# 07_ZYNQ_CAMERALINK.net
KiCad netlist of a schematic drawn in Altium Designer
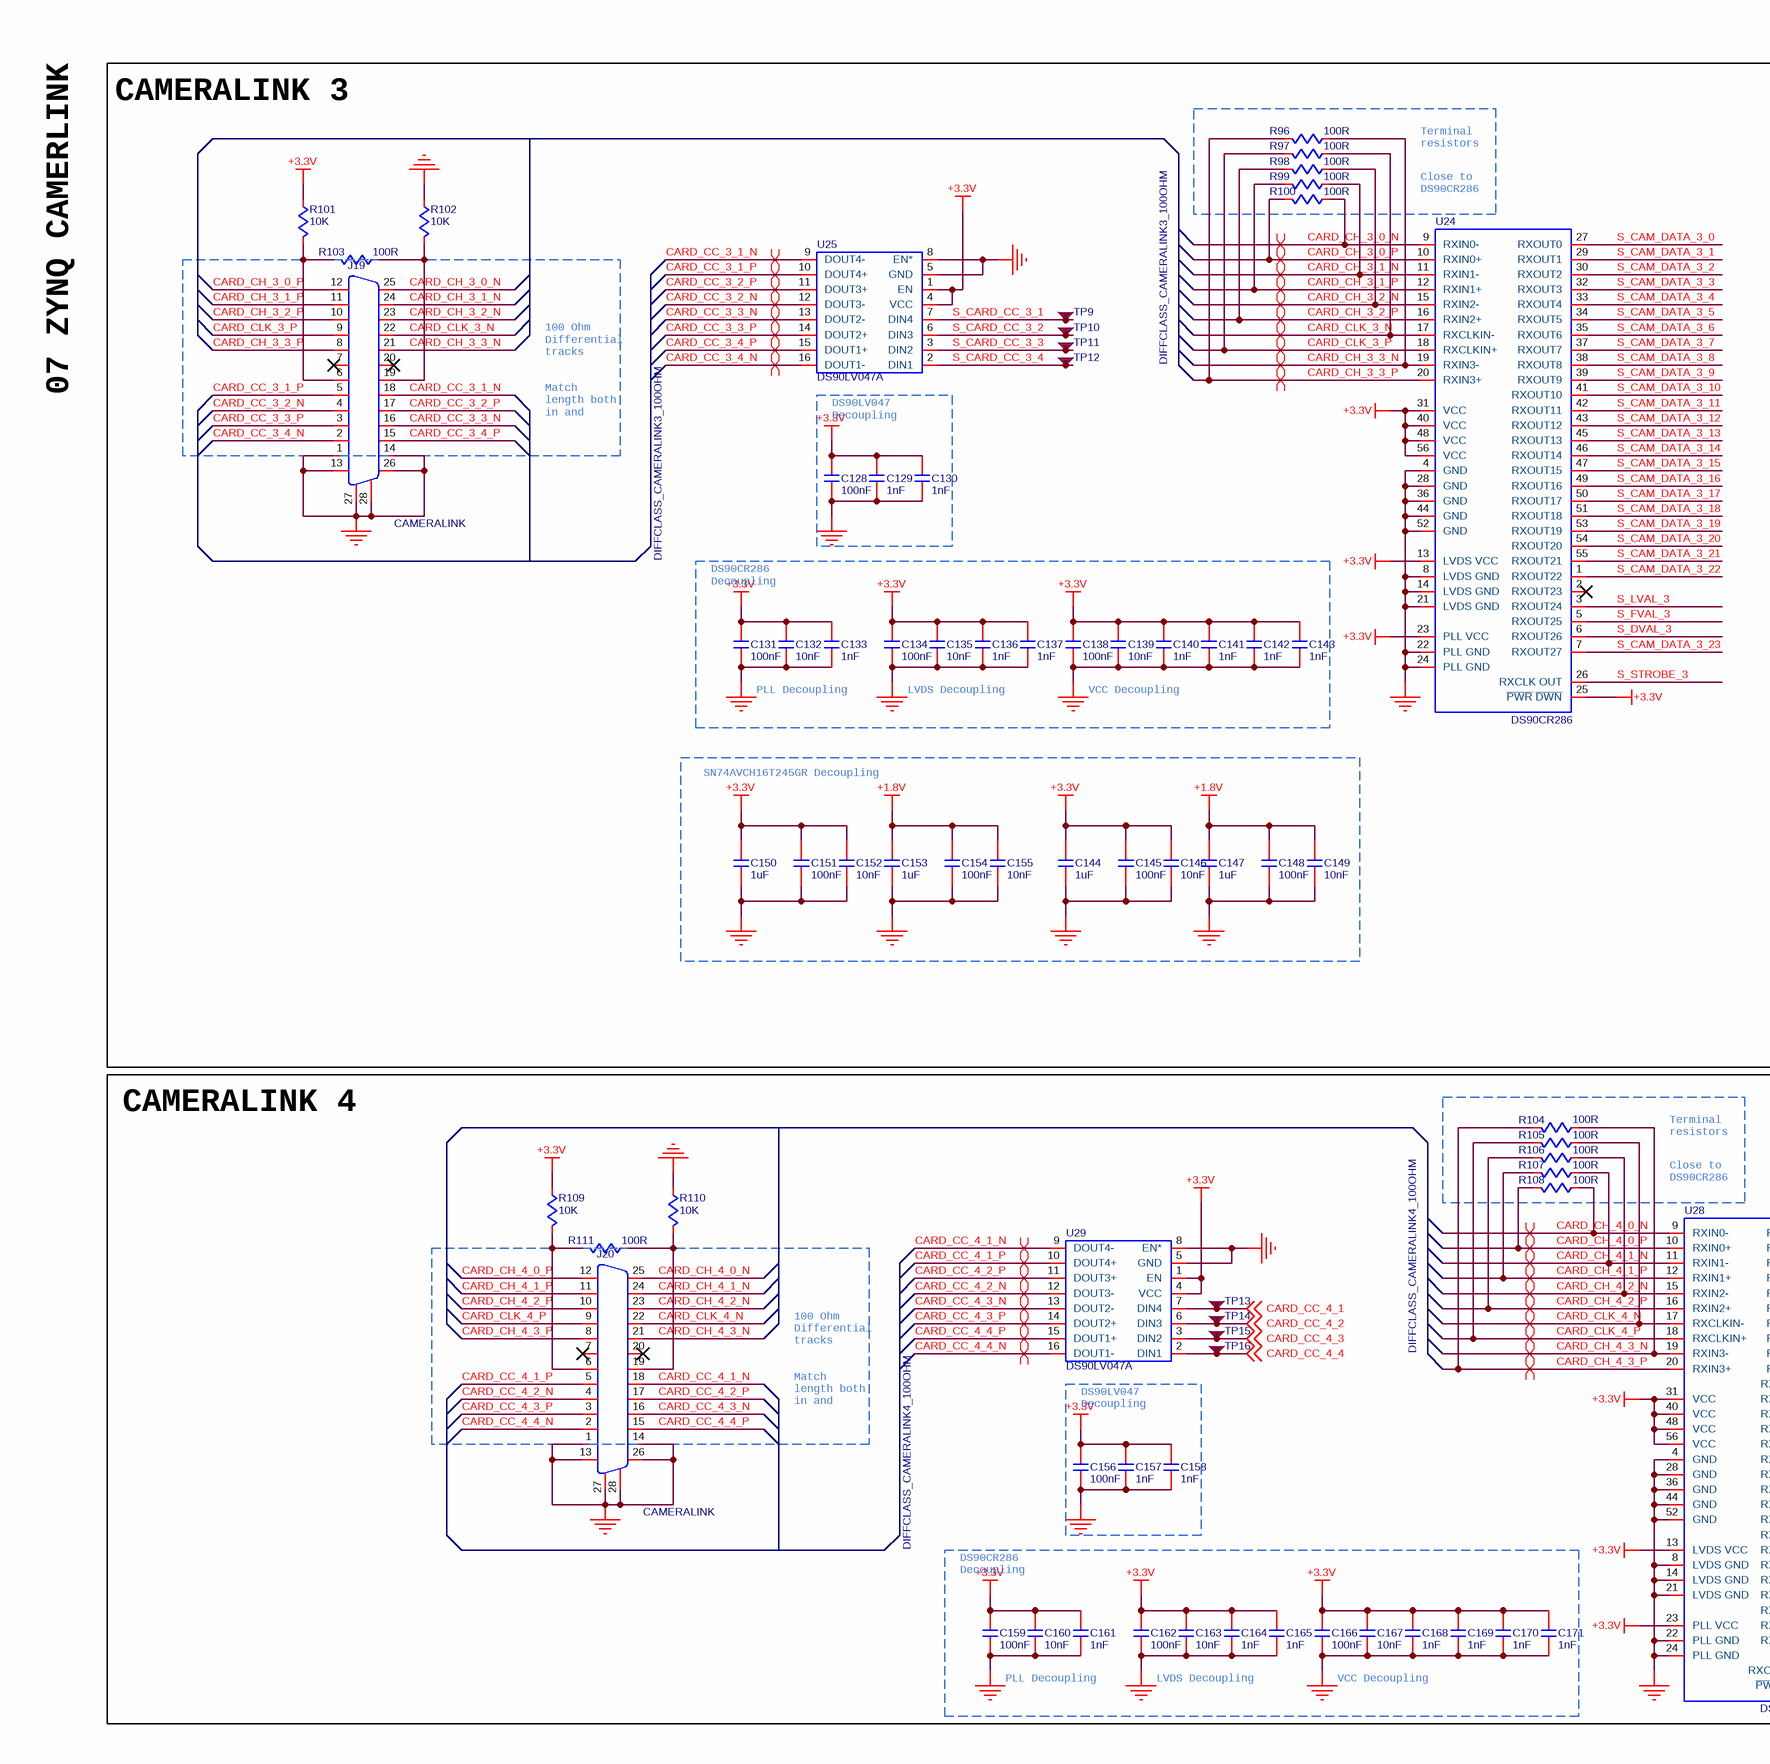
[diagram p0: 07_ZYNQ_CAMERALINK.SchDoc, left]
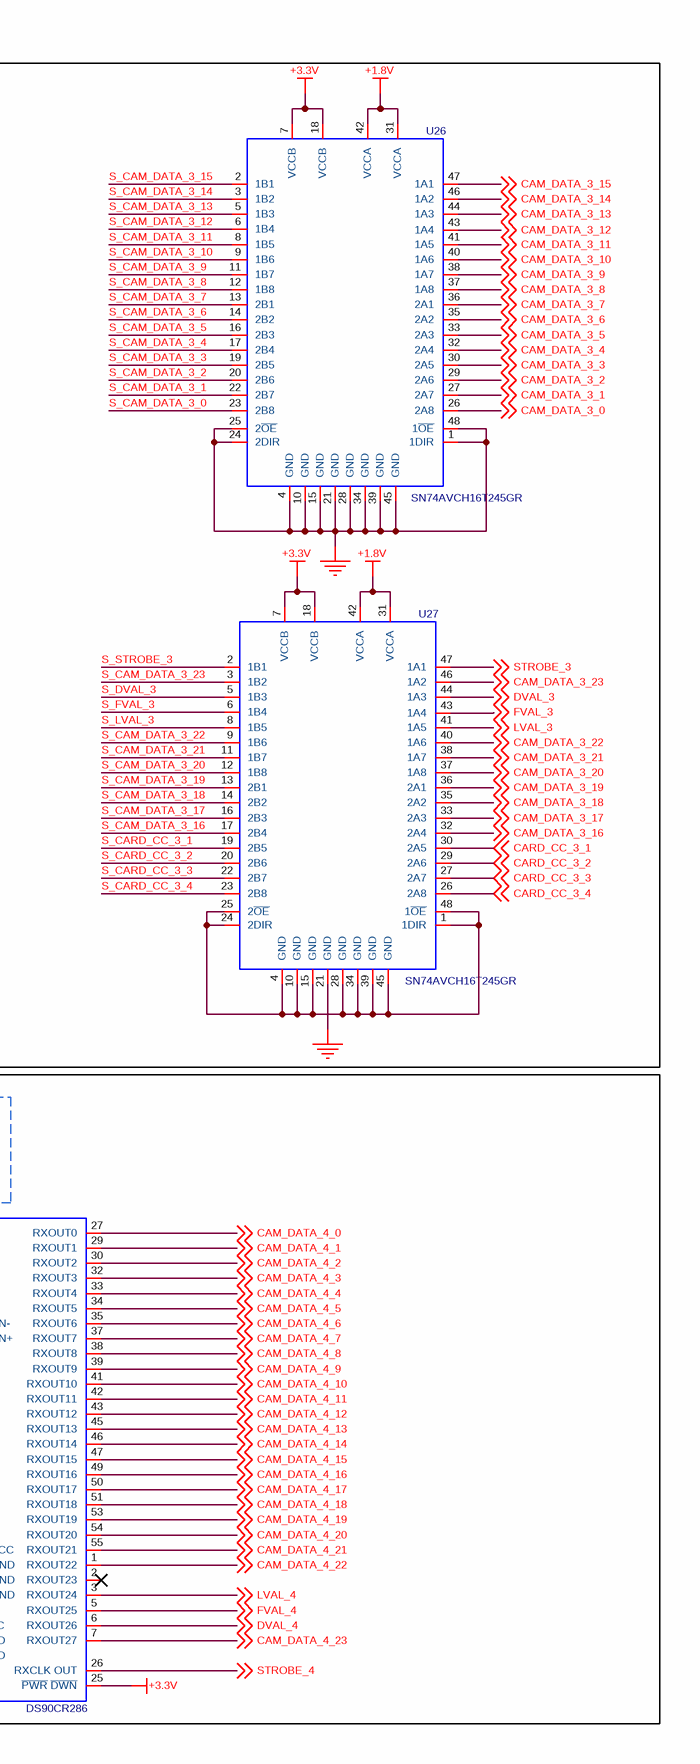
[diagram p1: 07_ZYNQ_CAMERALINK.SchDoc, right]

(export (version "E")
  (design (tool "Eeschema 10.0.6"))
  (components
    (comp (ref "C128")
      (value "100nF")
      (footprint "zynq:C0402")
      (fields (field (name "VOLTAGE") "25V") (field (name "Comment") "C-NOMO"))
      (libsource (lib "zynq") (part "C-NOMO"))
    )
    (comp (ref "C129")
      (value "1nF")
      (footprint "zynq:C0402")
      (fields (field (name "VOLTAGE") "25V") (field (name "Comment") "C-NOMO"))
      (libsource (lib "zynq") (part "C-NOMO"))
    )
    (comp (ref "C130")
      (value "1nF")
      (footprint "zynq:C0402")
      (fields (field (name "VOLTAGE") "25V") (field (name "Comment") "C-NOMO"))
      (libsource (lib "zynq") (part "C-NOMO"))
    )
    (comp (ref "C131")
      (value "100nF")
      (footprint "zynq:C0402")
      (fields (field (name "VOLTAGE") "25V") (field (name "Comment") "C-NOMO"))
      (libsource (lib "zynq") (part "C-NOMO"))
    )
    (comp (ref "C132")
      (value "10nF")
      (footprint "zynq:C0402")
      (fields (field (name "VOLTAGE") "25V") (field (name "Comment") "C-NOMO"))
      (libsource (lib "zynq") (part "C-NOMO"))
    )
    (comp (ref "C133")
      (value "1nF")
      (footprint "zynq:C0402")
      (fields (field (name "VOLTAGE") "25V") (field (name "Comment") "C-NOMO"))
      (libsource (lib "zynq") (part "C-NOMO"))
    )
    (comp (ref "C134")
      (value "100nF")
      (footprint "zynq:C0402")
      (fields (field (name "VOLTAGE") "25V") (field (name "Comment") "C-NOMO"))
      (libsource (lib "zynq") (part "C-NOMO"))
    )
    (comp (ref "C135")
      (value "10nF")
      (footprint "zynq:C0402")
      (fields (field (name "VOLTAGE") "25V") (field (name "Comment") "C-NOMO"))
      (libsource (lib "zynq") (part "C-NOMO"))
    )
    (comp (ref "C136")
      (value "1nF")
      (footprint "zynq:C0402")
      (fields (field (name "VOLTAGE") "25V") (field (name "Comment") "C-NOMO"))
      (libsource (lib "zynq") (part "C-NOMO"))
    )
    (comp (ref "C137")
      (value "1nF")
      (footprint "zynq:C0402")
      (fields (field (name "VOLTAGE") "25V") (field (name "Comment") "C-NOMO"))
      (libsource (lib "zynq") (part "C-NOMO"))
    )
    (comp (ref "C138")
      (value "100nF")
      (footprint "zynq:C0402")
      (fields (field (name "VOLTAGE") "25V") (field (name "Comment") "C-NOMO"))
      (libsource (lib "zynq") (part "C-NOMO"))
    )
    (comp (ref "C139")
      (value "10nF")
      (footprint "zynq:C0402")
      (fields (field (name "VOLTAGE") "25V") (field (name "Comment") "C-NOMO"))
      (libsource (lib "zynq") (part "C-NOMO"))
    )
    (comp (ref "C140")
      (value "1nF")
      (footprint "zynq:C0402")
      (fields (field (name "VOLTAGE") "25V") (field (name "Comment") "C-NOMO"))
      (libsource (lib "zynq") (part "C-NOMO"))
    )
    (comp (ref "C141")
      (value "1nF")
      (footprint "zynq:C0402")
      (fields (field (name "VOLTAGE") "25V") (field (name "Comment") "C-NOMO"))
      (libsource (lib "zynq") (part "C-NOMO"))
    )
    (comp (ref "C142")
      (value "1nF")
      (footprint "zynq:C0402")
      (fields (field (name "VOLTAGE") "25V") (field (name "Comment") "C-NOMO"))
      (libsource (lib "zynq") (part "C-NOMO"))
    )
    (comp (ref "C143")
      (value "1nF")
      (footprint "zynq:C0402")
      (fields (field (name "VOLTAGE") "25V") (field (name "Comment") "C-NOMO"))
      (libsource (lib "zynq") (part "C-NOMO"))
    )
    (comp (ref "C144")
      (value "1uF")
      (footprint "zynq:C0402")
      (fields (field (name "VOLTAGE") "25V") (field (name "Comment") "C-NOMO"))
      (libsource (lib "zynq") (part "C-NOMO"))
    )
    (comp (ref "C145")
      (value "100nF")
      (footprint "zynq:C0402")
      (fields (field (name "VOLTAGE") "25V") (field (name "Comment") "C-NOMO"))
      (libsource (lib "zynq") (part "C-NOMO"))
    )
    (comp (ref "C146")
      (value "10nF")
      (footprint "zynq:C0402")
      (fields (field (name "VOLTAGE") "25V") (field (name "Comment") "C-NOMO"))
      (libsource (lib "zynq") (part "C-NOMO"))
    )
    (comp (ref "C147")
      (value "1uF")
      (footprint "zynq:C0402")
      (fields (field (name "VOLTAGE") "25V") (field (name "Comment") "C-NOMO"))
      (libsource (lib "zynq") (part "C-NOMO"))
    )
    (comp (ref "C148")
      (value "100nF")
      (footprint "zynq:C0402")
      (fields (field (name "VOLTAGE") "25V") (field (name "Comment") "C-NOMO"))
      (libsource (lib "zynq") (part "C-NOMO"))
    )
    (comp (ref "C149")
      (value "10nF")
      (footprint "zynq:C0402")
      (fields (field (name "VOLTAGE") "25V") (field (name "Comment") "C-NOMO"))
      (libsource (lib "zynq") (part "C-NOMO"))
    )
    (comp (ref "C150")
      (value "1uF")
      (footprint "zynq:C0402")
      (fields (field (name "VOLTAGE") "25V") (field (name "Comment") "C-NOMO"))
      (libsource (lib "zynq") (part "C-NOMO"))
    )
    (comp (ref "C151")
      (value "100nF")
      (footprint "zynq:C0402")
      (fields (field (name "VOLTAGE") "25V") (field (name "Comment") "C-NOMO"))
      (libsource (lib "zynq") (part "C-NOMO"))
    )
    (comp (ref "C152")
      (value "10nF")
      (footprint "zynq:C0402")
      (fields (field (name "VOLTAGE") "25V") (field (name "Comment") "C-NOMO"))
      (libsource (lib "zynq") (part "C-NOMO"))
    )
    (comp (ref "C153")
      (value "1uF")
      (footprint "zynq:C0402")
      (fields (field (name "VOLTAGE") "25V") (field (name "Comment") "C-NOMO"))
      (libsource (lib "zynq") (part "C-NOMO"))
    )
    (comp (ref "C154")
      (value "100nF")
      (footprint "zynq:C0402")
      (fields (field (name "VOLTAGE") "25V") (field (name "Comment") "C-NOMO"))
      (libsource (lib "zynq") (part "C-NOMO"))
    )
    (comp (ref "C155")
      (value "10nF")
      (footprint "zynq:C0402")
      (fields (field (name "VOLTAGE") "25V") (field (name "Comment") "C-NOMO"))
      (libsource (lib "zynq") (part "C-NOMO"))
    )
    (comp (ref "C156")
      (value "100nF")
      (footprint "zynq:C0402")
      (fields (field (name "VOLTAGE") "25V") (field (name "Comment") "C-NOMO"))
      (libsource (lib "zynq") (part "C-NOMO"))
    )
    (comp (ref "C157")
      (value "1nF")
      (footprint "zynq:C0402")
      (fields (field (name "VOLTAGE") "25V") (field (name "Comment") "C-NOMO"))
      (libsource (lib "zynq") (part "C-NOMO"))
    )
    (comp (ref "C158")
      (value "1nF")
      (footprint "zynq:C0402")
      (fields (field (name "VOLTAGE") "25V") (field (name "Comment") "C-NOMO"))
      (libsource (lib "zynq") (part "C-NOMO"))
    )
    (comp (ref "C159")
      (value "100nF")
      (footprint "zynq:C0402")
      (fields (field (name "VOLTAGE") "25V") (field (name "Comment") "C-NOMO"))
      (libsource (lib "zynq") (part "C-NOMO"))
    )
    (comp (ref "C160")
      (value "10nF")
      (footprint "zynq:C0402")
      (fields (field (name "VOLTAGE") "25V") (field (name "Comment") "C-NOMO"))
      (libsource (lib "zynq") (part "C-NOMO"))
    )
    (comp (ref "C161")
      (value "1nF")
      (footprint "zynq:C0402")
      (fields (field (name "VOLTAGE") "25V") (field (name "Comment") "C-NOMO"))
      (libsource (lib "zynq") (part "C-NOMO"))
    )
    (comp (ref "C162")
      (value "100nF")
      (footprint "zynq:C0402")
      (fields (field (name "VOLTAGE") "25V") (field (name "Comment") "C-NOMO"))
      (libsource (lib "zynq") (part "C-NOMO"))
    )
    (comp (ref "C163")
      (value "10nF")
      (footprint "zynq:C0402")
      (fields (field (name "VOLTAGE") "25V") (field (name "Comment") "C-NOMO"))
      (libsource (lib "zynq") (part "C-NOMO"))
    )
    (comp (ref "C164")
      (value "1nF")
      (footprint "zynq:C0402")
      (fields (field (name "VOLTAGE") "25V") (field (name "Comment") "C-NOMO"))
      (libsource (lib "zynq") (part "C-NOMO"))
    )
    (comp (ref "C165")
      (value "1nF")
      (footprint "zynq:C0402")
      (fields (field (name "VOLTAGE") "25V") (field (name "Comment") "C-NOMO"))
      (libsource (lib "zynq") (part "C-NOMO"))
    )
    (comp (ref "C166")
      (value "100nF")
      (footprint "zynq:C0402")
      (fields (field (name "VOLTAGE") "25V") (field (name "Comment") "C-NOMO"))
      (libsource (lib "zynq") (part "C-NOMO"))
    )
    (comp (ref "C167")
      (value "10nF")
      (footprint "zynq:C0402")
      (fields (field (name "VOLTAGE") "25V") (field (name "Comment") "C-NOMO"))
      (libsource (lib "zynq") (part "C-NOMO"))
    )
    (comp (ref "C168")
      (value "1nF")
      (footprint "zynq:C0402")
      (fields (field (name "VOLTAGE") "25V") (field (name "Comment") "C-NOMO"))
      (libsource (lib "zynq") (part "C-NOMO"))
    )
    (comp (ref "C169")
      (value "1nF")
      (footprint "zynq:C0402")
      (fields (field (name "VOLTAGE") "25V") (field (name "Comment") "C-NOMO"))
      (libsource (lib "zynq") (part "C-NOMO"))
    )
    (comp (ref "C170")
      (value "1nF")
      (footprint "zynq:C0402")
      (fields (field (name "VOLTAGE") "25V") (field (name "Comment") "C-NOMO"))
      (libsource (lib "zynq") (part "C-NOMO"))
    )
    (comp (ref "C171")
      (value "1nF")
      (footprint "zynq:C0402")
      (fields (field (name "VOLTAGE") "25V") (field (name "Comment") "C-NOMO"))
      (libsource (lib "zynq") (part "C-NOMO"))
    )
    (comp (ref "J19")
      (value "CAMERALINK")
      (footprint "mw:CAMERALINK")
      (libsource (lib "zynq") (part "CAMERALINK"))
    )
    (comp (ref "J20")
      (value "CAMERALINK")
      (footprint "mw:CAMERALINK")
      (libsource (lib "zynq") (part "CAMERALINK"))
    )
    (comp (ref "R96")
      (value "100R")
      (footprint "zynq:R0402")
      (fields (field (name "Comment") "R"))
      (libsource (lib "zynq") (part "R"))
    )
    (comp (ref "R97")
      (value "100R")
      (footprint "zynq:R0402")
      (fields (field (name "Comment") "R"))
      (libsource (lib "zynq") (part "R"))
    )
    (comp (ref "R98")
      (value "100R")
      (footprint "zynq:R0402")
      (fields (field (name "Comment") "R"))
      (libsource (lib "zynq") (part "R"))
    )
    (comp (ref "R99")
      (value "100R")
      (footprint "zynq:R0402")
      (fields (field (name "Comment") "R"))
      (libsource (lib "zynq") (part "R"))
    )
    (comp (ref "R100")
      (value "100R")
      (footprint "zynq:R0402")
      (fields (field (name "Comment") "R"))
      (libsource (lib "zynq") (part "R"))
    )
    (comp (ref "R101")
      (value "10K")
      (footprint "zynq:R0402")
      (fields (field (name "Comment") "R"))
      (libsource (lib "zynq") (part "R"))
    )
    (comp (ref "R102")
      (value "10K")
      (footprint "zynq:R0402")
      (fields (field (name "Comment") "R"))
      (libsource (lib "zynq") (part "R"))
    )
    (comp (ref "R103")
      (value "100R")
      (footprint "zynq:R0402")
      (fields (field (name "Comment") "R"))
      (libsource (lib "zynq") (part "R"))
    )
    (comp (ref "R104")
      (value "100R")
      (footprint "zynq:R0402")
      (fields (field (name "Comment") "R"))
      (libsource (lib "zynq") (part "R"))
    )
    (comp (ref "R105")
      (value "100R")
      (footprint "zynq:R0402")
      (fields (field (name "Comment") "R"))
      (libsource (lib "zynq") (part "R"))
    )
    (comp (ref "R106")
      (value "100R")
      (footprint "zynq:R0402")
      (fields (field (name "Comment") "R"))
      (libsource (lib "zynq") (part "R"))
    )
    (comp (ref "R107")
      (value "100R")
      (footprint "zynq:R0402")
      (fields (field (name "Comment") "R"))
      (libsource (lib "zynq") (part "R"))
    )
    (comp (ref "R108")
      (value "100R")
      (footprint "zynq:R0402")
      (fields (field (name "Comment") "R"))
      (libsource (lib "zynq") (part "R"))
    )
    (comp (ref "R109")
      (value "10K")
      (footprint "zynq:R0402")
      (fields (field (name "Comment") "R"))
      (libsource (lib "zynq") (part "R"))
    )
    (comp (ref "R110")
      (value "10K")
      (footprint "zynq:R0402")
      (fields (field (name "Comment") "R"))
      (libsource (lib "zynq") (part "R"))
    )
    (comp (ref "R111")
      (value "100R")
      (footprint "zynq:R0402")
      (fields (field (name "Comment") "R"))
      (libsource (lib "zynq") (part "R"))
    )
    (comp (ref "TP9") (value "TP") (footprint "zynq:TP") (libsource (lib "zynq") (part "TP")))
    (comp (ref "TP10") (value "TP") (footprint "zynq:TP") (libsource (lib "zynq") (part "TP")))
    (comp (ref "TP11") (value "TP") (footprint "zynq:TP") (libsource (lib "zynq") (part "TP")))
    (comp (ref "TP12") (value "TP") (footprint "zynq:TP") (libsource (lib "zynq") (part "TP")))
    (comp (ref "TP13") (value "TP") (footprint "zynq:TP") (libsource (lib "zynq") (part "TP")))
    (comp (ref "TP14") (value "TP") (footprint "zynq:TP") (libsource (lib "zynq") (part "TP")))
    (comp (ref "TP15") (value "TP") (footprint "zynq:TP") (libsource (lib "zynq") (part "TP")))
    (comp (ref "TP16") (value "TP") (footprint "zynq:TP") (libsource (lib "zynq") (part "TP")))
    (comp (ref "U24")
      (value "DS90CR286")
      (footprint "zynq:DS90CR286")
      (libsource (lib "zynq") (part "DS90CR286"))
    )
    (comp (ref "U25")
      (value "DS90LV047A")
      (footprint "zynq:DS90LV047")
      (libsource (lib "zynq") (part "DS90LV047A"))
    )
    (comp (ref "U26")
      (value "SN74AVCH16T245GR")
      (footprint "SN74AVCH16T245GR")
      (libsource (lib "zynq") (part "SN74AVCH16T245GR"))
    )
    (comp (ref "U27")
      (value "SN74AVCH16T245GR")
      (footprint "SN74AVCH16T245GR")
      (libsource (lib "zynq") (part "SN74AVCH16T245GR"))
    )
    (comp (ref "U28")
      (value "DS90CR286")
      (footprint "zynq:DS90CR286")
      (libsource (lib "zynq") (part "DS90CR286"))
    )
    (comp (ref "U29")
      (value "DS90LV047A")
      (footprint "zynq:DS90LV047")
      (libsource (lib "zynq") (part "DS90LV047A"))
    )
  )
  (nets
    (net (code "1") (name "+1.8V") (class "Default")
      (node (ref "C147") (pin "2") (pinfunction "2_2") (pintype "passive"))
      (node (ref "C148") (pin "2") (pinfunction "2_2") (pintype "passive"))
      (node (ref "C149") (pin "2") (pinfunction "2_2") (pintype "passive"))
      (node (ref "C153") (pin "2") (pinfunction "2_2") (pintype "passive"))
      (node (ref "C154") (pin "2") (pinfunction "2_2") (pintype "passive"))
      (node (ref "C155") (pin "2") (pinfunction "2_2") (pintype "passive"))
      (node (ref "U26") (pin "31") (pinfunction "VCCA_31") (pintype "passive"))
      (node (ref "U26") (pin "42") (pinfunction "VCCA_42") (pintype "passive"))
      (node (ref "U27") (pin "31") (pinfunction "VCCA_31") (pintype "passive"))
      (node (ref "U27") (pin "42") (pinfunction "VCCA_42") (pintype "passive"))
    )
    (net (code "2") (name "+3.3V") (class "Default")
      (node (ref "C128") (pin "2") (pinfunction "2_2") (pintype "passive"))
      (node (ref "C129") (pin "2") (pinfunction "2_2") (pintype "passive"))
      (node (ref "C130") (pin "2") (pinfunction "2_2") (pintype "passive"))
      (node (ref "C131") (pin "2") (pinfunction "2_2") (pintype "passive"))
      (node (ref "C132") (pin "2") (pinfunction "2_2") (pintype "passive"))
      (node (ref "C133") (pin "2") (pinfunction "2_2") (pintype "passive"))
      (node (ref "C134") (pin "2") (pinfunction "2_2") (pintype "passive"))
      (node (ref "C135") (pin "2") (pinfunction "2_2") (pintype "passive"))
      (node (ref "C136") (pin "2") (pinfunction "2_2") (pintype "passive"))
      (node (ref "C137") (pin "2") (pinfunction "2_2") (pintype "passive"))
      (node (ref "C138") (pin "2") (pinfunction "2_2") (pintype "passive"))
      (node (ref "C139") (pin "2") (pinfunction "2_2") (pintype "passive"))
      (node (ref "C140") (pin "2") (pinfunction "2_2") (pintype "passive"))
      (node (ref "C141") (pin "2") (pinfunction "2_2") (pintype "passive"))
      (node (ref "C142") (pin "2") (pinfunction "2_2") (pintype "passive"))
      (node (ref "C143") (pin "2") (pinfunction "2_2") (pintype "passive"))
      (node (ref "C144") (pin "2") (pinfunction "2_2") (pintype "passive"))
      (node (ref "C145") (pin "2") (pinfunction "2_2") (pintype "passive"))
      (node (ref "C146") (pin "2") (pinfunction "2_2") (pintype "passive"))
      (node (ref "C150") (pin "2") (pinfunction "2_2") (pintype "passive"))
      (node (ref "C151") (pin "2") (pinfunction "2_2") (pintype "passive"))
      (node (ref "C152") (pin "2") (pinfunction "2_2") (pintype "passive"))
      (node (ref "C156") (pin "2") (pinfunction "2_2") (pintype "passive"))
      (node (ref "C157") (pin "2") (pinfunction "2_2") (pintype "passive"))
      (node (ref "C158") (pin "2") (pinfunction "2_2") (pintype "passive"))
      (node (ref "C159") (pin "2") (pinfunction "2_2") (pintype "passive"))
      (node (ref "C160") (pin "2") (pinfunction "2_2") (pintype "passive"))
      (node (ref "C161") (pin "2") (pinfunction "2_2") (pintype "passive"))
      (node (ref "C162") (pin "2") (pinfunction "2_2") (pintype "passive"))
      (node (ref "C163") (pin "2") (pinfunction "2_2") (pintype "passive"))
      (node (ref "C164") (pin "2") (pinfunction "2_2") (pintype "passive"))
      (node (ref "C165") (pin "2") (pinfunction "2_2") (pintype "passive"))
      (node (ref "C166") (pin "2") (pinfunction "2_2") (pintype "passive"))
      (node (ref "C167") (pin "2") (pinfunction "2_2") (pintype "passive"))
      (node (ref "C168") (pin "2") (pinfunction "2_2") (pintype "passive"))
      (node (ref "C169") (pin "2") (pinfunction "2_2") (pintype "passive"))
      (node (ref "C170") (pin "2") (pinfunction "2_2") (pintype "passive"))
      (node (ref "C171") (pin "2") (pinfunction "2_2") (pintype "passive"))
      (node (ref "R101") (pin "2") (pinfunction "2_2") (pintype "passive"))
      (node (ref "R109") (pin "2") (pinfunction "2_2") (pintype "passive"))
      (node (ref "U24") (pin "13") (pinfunction "LVDS_VCC_13") (pintype "passive"))
      (node (ref "U24") (pin "23") (pinfunction "PLL_VCC_23") (pintype "passive"))
      (node (ref "U24") (pin "25") (pinfunction "~{PWR}_~{DWN}_25") (pintype "passive"))
      (node (ref "U24") (pin "31") (pinfunction "VCC_31") (pintype "passive"))
      (node (ref "U24") (pin "40") (pinfunction "VCC_40") (pintype "passive"))
      (node (ref "U24") (pin "48") (pinfunction "VCC_48") (pintype "passive"))
      (node (ref "U24") (pin "56") (pinfunction "VCC_56") (pintype "passive"))
      (node (ref "U25") (pin "1") (pinfunction "EN_1") (pintype "passive"))
      (node (ref "U25") (pin "4") (pinfunction "VCC_4") (pintype "passive"))
      (node (ref "U26") (pin "18") (pinfunction "VCCB_18") (pintype "passive"))
      (node (ref "U26") (pin "7") (pinfunction "VCCB_7") (pintype "passive"))
      (node (ref "U27") (pin "18") (pinfunction "VCCB_18") (pintype "passive"))
      (node (ref "U27") (pin "7") (pinfunction "VCCB_7") (pintype "passive"))
      (node (ref "U28") (pin "13") (pinfunction "LVDS_VCC_13") (pintype "passive"))
      (node (ref "U28") (pin "23") (pinfunction "PLL_VCC_23") (pintype "passive"))
      (node (ref "U28") (pin "25") (pinfunction "~{PWR}_~{DWN}_25") (pintype "passive"))
      (node (ref "U28") (pin "31") (pinfunction "VCC_31") (pintype "passive"))
      (node (ref "U28") (pin "40") (pinfunction "VCC_40") (pintype "passive"))
      (node (ref "U28") (pin "48") (pinfunction "VCC_48") (pintype "passive"))
      (node (ref "U28") (pin "56") (pinfunction "VCC_56") (pintype "passive"))
      (node (ref "U29") (pin "1") (pinfunction "EN_1") (pintype "passive"))
      (node (ref "U29") (pin "4") (pinfunction "VCC_4") (pintype "passive"))
    )
    (net (code "3") (name "/CARD_CC_3_1_N") (class "Default")
      (node (ref "J19") (pin "18") (pintype "passive"))
      (node (ref "U25") (pin "9") (pinfunction "DOUT4-_9") (pintype "passive"))
    )
    (net (code "4") (name "/CARD_CC_3_1_P") (class "Default")
      (node (ref "J19") (pin "5") (pintype "passive"))
      (node (ref "U25") (pin "10") (pinfunction "DOUT4+_10") (pintype "passive"))
    )
    (net (code "5") (name "/CARD_CC_3_2_N") (class "Default")
      (node (ref "J19") (pin "4") (pintype "passive"))
      (node (ref "U25") (pin "12") (pinfunction "DOUT3-_12") (pintype "passive"))
    )
    (net (code "6") (name "/CARD_CC_3_2_P") (class "Default")
      (node (ref "J19") (pin "17") (pintype "passive"))
      (node (ref "U25") (pin "11") (pinfunction "DOUT3+_11") (pintype "passive"))
    )
    (net (code "7") (name "/CARD_CC_3_3_N") (class "Default")
      (node (ref "J19") (pin "16") (pintype "passive"))
      (node (ref "U25") (pin "13") (pinfunction "DOUT2-_13") (pintype "passive"))
    )
    (net (code "8") (name "/CARD_CC_3_3_P") (class "Default")
      (node (ref "J19") (pin "3") (pintype "passive"))
      (node (ref "U25") (pin "14") (pinfunction "DOUT2+_14") (pintype "passive"))
    )
    (net (code "9") (name "/CARD_CC_3_4_N") (class "Default")
      (node (ref "J19") (pin "2") (pintype "passive"))
      (node (ref "U25") (pin "16") (pinfunction "DOUT1-_16") (pintype "passive"))
    )
    (net (code "10") (name "/CARD_CC_3_4_P") (class "Default")
      (node (ref "J19") (pin "15") (pintype "passive"))
      (node (ref "U25") (pin "15") (pinfunction "DOUT1+_15") (pintype "passive"))
    )
    (net (code "11") (name "/CARD_CC_4_1_N") (class "Default")
      (node (ref "J20") (pin "18") (pintype "passive"))
      (node (ref "U29") (pin "9") (pinfunction "DOUT4-_9") (pintype "passive"))
    )
    (net (code "12") (name "/CARD_CC_4_1_P") (class "Default")
      (node (ref "J20") (pin "5") (pintype "passive"))
      (node (ref "U29") (pin "10") (pinfunction "DOUT4+_10") (pintype "passive"))
    )
    (net (code "13") (name "/CARD_CC_4_2_N") (class "Default")
      (node (ref "J20") (pin "4") (pintype "passive"))
      (node (ref "U29") (pin "12") (pinfunction "DOUT3-_12") (pintype "passive"))
    )
    (net (code "14") (name "/CARD_CC_4_2_P") (class "Default")
      (node (ref "J20") (pin "17") (pintype "passive"))
      (node (ref "U29") (pin "11") (pinfunction "DOUT3+_11") (pintype "passive"))
    )
    (net (code "15") (name "/CARD_CC_4_3_N") (class "Default")
      (node (ref "J20") (pin "16") (pintype "passive"))
      (node (ref "U29") (pin "13") (pinfunction "DOUT2-_13") (pintype "passive"))
    )
    (net (code "16") (name "/CARD_CC_4_3_P") (class "Default")
      (node (ref "J20") (pin "3") (pintype "passive"))
      (node (ref "U29") (pin "14") (pinfunction "DOUT2+_14") (pintype "passive"))
    )
    (net (code "17") (name "/CARD_CC_4_4_N") (class "Default")
      (node (ref "J20") (pin "2") (pintype "passive"))
      (node (ref "U29") (pin "16") (pinfunction "DOUT1-_16") (pintype "passive"))
    )
    (net (code "18") (name "/CARD_CC_4_4_P") (class "Default")
      (node (ref "J20") (pin "15") (pintype "passive"))
      (node (ref "U29") (pin "15") (pinfunction "DOUT1+_15") (pintype "passive"))
    )
    (net (code "19") (name "/CARD_CH_3_0_N") (class "Default")
      (node (ref "J19") (pin "25") (pintype "passive"))
      (node (ref "R100") (pin "2") (pinfunction "2_2") (pintype "passive"))
      (node (ref "U24") (pin "9") (pinfunction "RXIN0-_9") (pintype "passive"))
    )
    (net (code "20") (name "/CARD_CH_3_0_P") (class "Default")
      (node (ref "J19") (pin "12") (pintype "passive"))
      (node (ref "R100") (pin "1") (pinfunction "1_1") (pintype "passive"))
      (node (ref "U24") (pin "10") (pinfunction "RXIN0+_10") (pintype "passive"))
    )
    (net (code "21") (name "/CARD_CH_3_1_N") (class "Default")
      (node (ref "J19") (pin "24") (pintype "passive"))
      (node (ref "R99") (pin "2") (pinfunction "2_2") (pintype "passive"))
      (node (ref "U24") (pin "11") (pinfunction "RXIN1-_11") (pintype "passive"))
    )
    (net (code "22") (name "/CARD_CH_3_1_P") (class "Default")
      (node (ref "J19") (pin "11") (pintype "passive"))
      (node (ref "R99") (pin "1") (pinfunction "1_1") (pintype "passive"))
      (node (ref "U24") (pin "12") (pinfunction "RXIN1+_12") (pintype "passive"))
    )
    (net (code "23") (name "/CARD_CH_3_2_N") (class "Default")
      (node (ref "J19") (pin "23") (pintype "passive"))
      (node (ref "R98") (pin "2") (pinfunction "2_2") (pintype "passive"))
      (node (ref "U24") (pin "15") (pinfunction "RXIN2-_15") (pintype "passive"))
    )
    (net (code "24") (name "/CARD_CH_3_2_P") (class "Default")
      (node (ref "J19") (pin "10") (pintype "passive"))
      (node (ref "R98") (pin "1") (pinfunction "1_1") (pintype "passive"))
      (node (ref "U24") (pin "16") (pinfunction "RXIN2+_16") (pintype "passive"))
    )
    (net (code "25") (name "/CARD_CH_3_3_N") (class "Default")
      (node (ref "J19") (pin "21") (pintype "passive"))
      (node (ref "R96") (pin "2") (pinfunction "2_2") (pintype "passive"))
      (node (ref "U24") (pin "19") (pinfunction "RXIN3-_19") (pintype "passive"))
    )
    (net (code "26") (name "/CARD_CH_3_3_P") (class "Default")
      (node (ref "J19") (pin "8") (pintype "passive"))
      (node (ref "R96") (pin "1") (pinfunction "1_1") (pintype "passive"))
      (node (ref "U24") (pin "20") (pinfunction "RXIN3+_20") (pintype "passive"))
    )
    (net (code "27") (name "/CARD_CH_4_0_N") (class "Default")
      (node (ref "J20") (pin "25") (pintype "passive"))
      (node (ref "R108") (pin "2") (pinfunction "2_2") (pintype "passive"))
      (node (ref "U28") (pin "9") (pinfunction "RXIN0-_9") (pintype "passive"))
    )
    (net (code "28") (name "/CARD_CH_4_0_P") (class "Default")
      (node (ref "J20") (pin "12") (pintype "passive"))
      (node (ref "R108") (pin "1") (pinfunction "1_1") (pintype "passive"))
      (node (ref "U28") (pin "10") (pinfunction "RXIN0+_10") (pintype "passive"))
    )
    (net (code "29") (name "/CARD_CH_4_1_N") (class "Default")
      (node (ref "J20") (pin "24") (pintype "passive"))
      (node (ref "R107") (pin "2") (pinfunction "2_2") (pintype "passive"))
      (node (ref "U28") (pin "11") (pinfunction "RXIN1-_11") (pintype "passive"))
    )
    (net (code "30") (name "/CARD_CH_4_1_P") (class "Default")
      (node (ref "J20") (pin "11") (pintype "passive"))
      (node (ref "R107") (pin "1") (pinfunction "1_1") (pintype "passive"))
      (node (ref "U28") (pin "12") (pinfunction "RXIN1+_12") (pintype "passive"))
    )
    (net (code "31") (name "/CARD_CH_4_2_N") (class "Default")
      (node (ref "J20") (pin "23") (pintype "passive"))
      (node (ref "R106") (pin "2") (pinfunction "2_2") (pintype "passive"))
      (node (ref "U28") (pin "15") (pinfunction "RXIN2-_15") (pintype "passive"))
    )
    (net (code "32") (name "/CARD_CH_4_2_P") (class "Default")
      (node (ref "J20") (pin "10") (pintype "passive"))
      (node (ref "R106") (pin "1") (pinfunction "1_1") (pintype "passive"))
      (node (ref "U28") (pin "16") (pinfunction "RXIN2+_16") (pintype "passive"))
    )
    (net (code "33") (name "/CARD_CH_4_3_N") (class "Default")
      (node (ref "J20") (pin "21") (pintype "passive"))
      (node (ref "R104") (pin "2") (pinfunction "2_2") (pintype "passive"))
      (node (ref "U28") (pin "19") (pinfunction "RXIN3-_19") (pintype "passive"))
    )
    (net (code "34") (name "/CARD_CH_4_3_P") (class "Default")
      (node (ref "J20") (pin "8") (pintype "passive"))
      (node (ref "R104") (pin "1") (pinfunction "1_1") (pintype "passive"))
      (node (ref "U28") (pin "20") (pinfunction "RXIN3+_20") (pintype "passive"))
    )
    (net (code "35") (name "/CARD_CLK_3_N") (class "Default")
      (node (ref "J19") (pin "22") (pintype "passive"))
      (node (ref "R97") (pin "2") (pinfunction "2_2") (pintype "passive"))
      (node (ref "U24") (pin "17") (pinfunction "RXCLKIN-_17") (pintype "passive"))
    )
    (net (code "36") (name "/CARD_CLK_3_P") (class "Default")
      (node (ref "J19") (pin "9") (pintype "passive"))
      (node (ref "R97") (pin "1") (pinfunction "1_1") (pintype "passive"))
      (node (ref "U24") (pin "18") (pinfunction "RXCLKIN+_18") (pintype "passive"))
    )
    (net (code "37") (name "/CARD_CLK_4_N") (class "Default")
      (node (ref "J20") (pin "22") (pintype "passive"))
      (node (ref "R105") (pin "2") (pinfunction "2_2") (pintype "passive"))
      (node (ref "U28") (pin "17") (pinfunction "RXCLKIN-_17") (pintype "passive"))
    )
    (net (code "38") (name "/CARD_CLK_4_P") (class "Default")
      (node (ref "J20") (pin "9") (pintype "passive"))
      (node (ref "R105") (pin "1") (pinfunction "1_1") (pintype "passive"))
      (node (ref "U28") (pin "18") (pinfunction "RXCLKIN+_18") (pintype "passive"))
    )
    (net (code "39") (name "/S_CAM_DATA_3_0") (class "Default")
      (node (ref "U24") (pin "27") (pinfunction "RXOUT0_27") (pintype "passive"))
      (node (ref "U26") (pin "23") (pinfunction "2B8_23") (pintype "passive"))
    )
    (net (code "40") (name "/S_CAM_DATA_3_1") (class "Default")
      (node (ref "U24") (pin "29") (pinfunction "RXOUT1_29") (pintype "passive"))
      (node (ref "U26") (pin "22") (pinfunction "2B7_22") (pintype "passive"))
    )
    (net (code "41") (name "/S_CAM_DATA_3_2") (class "Default")
      (node (ref "U24") (pin "30") (pinfunction "RXOUT2_30") (pintype "passive"))
      (node (ref "U26") (pin "20") (pinfunction "2B6_20") (pintype "passive"))
    )
    (net (code "42") (name "/S_CAM_DATA_3_3") (class "Default")
      (node (ref "U24") (pin "32") (pinfunction "RXOUT3_32") (pintype "passive"))
      (node (ref "U26") (pin "19") (pinfunction "2B5_19") (pintype "passive"))
    )
    (net (code "43") (name "/S_CAM_DATA_3_4") (class "Default")
      (node (ref "U24") (pin "33") (pinfunction "RXOUT4_33") (pintype "passive"))
      (node (ref "U26") (pin "17") (pinfunction "2B4_17") (pintype "passive"))
    )
    (net (code "44") (name "/S_CAM_DATA_3_5") (class "Default")
      (node (ref "U24") (pin "34") (pinfunction "RXOUT5_34") (pintype "passive"))
      (node (ref "U26") (pin "16") (pinfunction "2B3_16") (pintype "passive"))
    )
    (net (code "45") (name "/S_CAM_DATA_3_6") (class "Default")
      (node (ref "U24") (pin "35") (pinfunction "RXOUT6_35") (pintype "passive"))
      (node (ref "U26") (pin "14") (pinfunction "2B2_14") (pintype "passive"))
    )
    (net (code "46") (name "/S_CAM_DATA_3_7") (class "Default")
      (node (ref "U24") (pin "37") (pinfunction "RXOUT7_37") (pintype "passive"))
      (node (ref "U26") (pin "13") (pinfunction "2B1_13") (pintype "passive"))
    )
    (net (code "47") (name "/S_CAM_DATA_3_8") (class "Default")
      (node (ref "U24") (pin "38") (pinfunction "RXOUT8_38") (pintype "passive"))
      (node (ref "U26") (pin "12") (pinfunction "1B8_12") (pintype "passive"))
    )
    (net (code "48") (name "/S_CAM_DATA_3_9") (class "Default")
      (node (ref "U24") (pin "39") (pinfunction "RXOUT9_39") (pintype "passive"))
      (node (ref "U26") (pin "11") (pinfunction "1B7_11") (pintype "passive"))
    )
    (net (code "49") (name "/S_CAM_DATA_3_10") (class "Default")
      (node (ref "U24") (pin "41") (pinfunction "RXOUT10_41") (pintype "passive"))
      (node (ref "U26") (pin "9") (pinfunction "1B6_9") (pintype "passive"))
    )
    (net (code "50") (name "/S_CAM_DATA_3_11") (class "Default")
      (node (ref "U24") (pin "42") (pinfunction "RXOUT11_42") (pintype "passive"))
      (node (ref "U26") (pin "8") (pinfunction "1B5_8") (pintype "passive"))
    )
    (net (code "51") (name "/S_CAM_DATA_3_12") (class "Default")
      (node (ref "U24") (pin "43") (pinfunction "RXOUT12_43") (pintype "passive"))
      (node (ref "U26") (pin "6") (pinfunction "1B4_6") (pintype "passive"))
    )
    (net (code "52") (name "/S_CAM_DATA_3_13") (class "Default")
      (node (ref "U24") (pin "45") (pinfunction "RXOUT13_45") (pintype "passive"))
      (node (ref "U26") (pin "5") (pinfunction "1B3_5") (pintype "passive"))
    )
    (net (code "53") (name "/S_CAM_DATA_3_14") (class "Default")
      (node (ref "U24") (pin "46") (pinfunction "RXOUT14_46") (pintype "passive"))
      (node (ref "U26") (pin "3") (pinfunction "1B2_3") (pintype "passive"))
    )
    (net (code "54") (name "/S_CAM_DATA_3_15") (class "Default")
      (node (ref "U24") (pin "47") (pinfunction "RXOUT15_47") (pintype "passive"))
      (node (ref "U26") (pin "2") (pinfunction "1B1_2") (pintype "passive"))
    )
    (net (code "55") (name "/S_CAM_DATA_3_16") (class "Default")
      (node (ref "U24") (pin "49") (pinfunction "RXOUT16_49") (pintype "passive"))
      (node (ref "U27") (pin "17") (pinfunction "2B4_17") (pintype "passive"))
    )
    (net (code "56") (name "/S_CAM_DATA_3_17") (class "Default")
      (node (ref "U24") (pin "50") (pinfunction "RXOUT17_50") (pintype "passive"))
      (node (ref "U27") (pin "16") (pinfunction "2B3_16") (pintype "passive"))
    )
    (net (code "57") (name "/S_CAM_DATA_3_18") (class "Default")
      (node (ref "U24") (pin "51") (pinfunction "RXOUT18_51") (pintype "passive"))
      (node (ref "U27") (pin "14") (pinfunction "2B2_14") (pintype "passive"))
    )
    (net (code "58") (name "/S_CAM_DATA_3_19") (class "Default")
      (node (ref "U24") (pin "53") (pinfunction "RXOUT19_53") (pintype "passive"))
      (node (ref "U27") (pin "13") (pinfunction "2B1_13") (pintype "passive"))
    )
    (net (code "59") (name "/S_CAM_DATA_3_20") (class "Default")
      (node (ref "U24") (pin "54") (pinfunction "RXOUT20_54") (pintype "passive"))
      (node (ref "U27") (pin "12") (pinfunction "1B8_12") (pintype "passive"))
    )
    (net (code "60") (name "/S_CAM_DATA_3_21") (class "Default")
      (node (ref "U24") (pin "55") (pinfunction "RXOUT21_55") (pintype "passive"))
      (node (ref "U27") (pin "11") (pinfunction "1B7_11") (pintype "passive"))
    )
    (net (code "61") (name "/S_CAM_DATA_3_22") (class "Default")
      (node (ref "U24") (pin "1") (pinfunction "RXOUT22_1") (pintype "passive"))
      (node (ref "U27") (pin "9") (pinfunction "1B6_9") (pintype "passive"))
    )
    (net (code "62") (name "/S_CAM_DATA_3_23") (class "Default")
      (node (ref "U24") (pin "7") (pinfunction "RXOUT27_7") (pintype "passive"))
      (node (ref "U27") (pin "3") (pinfunction "1B2_3") (pintype "passive"))
    )
    (net (code "63") (name "/S_CARD_CC_3_1") (class "Default")
      (node (ref "TP9") (pin "0") (pintype "passive"))
      (node (ref "U25") (pin "7") (pinfunction "DIN4_7") (pintype "passive"))
      (node (ref "U27") (pin "19") (pinfunction "2B5_19") (pintype "passive"))
    )
    (net (code "64") (name "/S_CARD_CC_3_2") (class "Default")
      (node (ref "TP10") (pin "0") (pintype "passive"))
      (node (ref "U25") (pin "6") (pinfunction "DIN3_6") (pintype "passive"))
      (node (ref "U27") (pin "20") (pinfunction "2B6_20") (pintype "passive"))
    )
    (net (code "65") (name "/S_CARD_CC_3_3") (class "Default")
      (node (ref "TP11") (pin "0") (pintype "passive"))
      (node (ref "U25") (pin "3") (pinfunction "DIN2_3") (pintype "passive"))
      (node (ref "U27") (pin "22") (pinfunction "2B7_22") (pintype "passive"))
    )
    (net (code "66") (name "/S_CARD_CC_3_4") (class "Default")
      (node (ref "TP12") (pin "0") (pintype "passive"))
      (node (ref "U25") (pin "2") (pinfunction "DIN1_2") (pintype "passive"))
      (node (ref "U27") (pin "23") (pinfunction "2B8_23") (pintype "passive"))
    )
    (net (code "67") (name "/S_DVAL_3") (class "Default")
      (node (ref "U24") (pin "6") (pinfunction "RXOUT26_6") (pintype "passive"))
      (node (ref "U27") (pin "5") (pinfunction "1B3_5") (pintype "passive"))
    )
    (net (code "68") (name "/S_FVAL_3") (class "Default")
      (node (ref "U24") (pin "5") (pinfunction "RXOUT25_5") (pintype "passive"))
      (node (ref "U27") (pin "6") (pinfunction "1B4_6") (pintype "passive"))
    )
    (net (code "69") (name "/S_LVAL_3") (class "Default")
      (node (ref "U24") (pin "3") (pinfunction "RXOUT24_3") (pintype "passive"))
      (node (ref "U27") (pin "8") (pinfunction "1B5_8") (pintype "passive"))
    )
    (net (code "70") (name "/S_STROBE_3") (class "Default")
      (node (ref "U24") (pin "26") (pinfunction "RXCLK_OUT_26") (pintype "passive"))
      (node (ref "U27") (pin "2") (pinfunction "1B1_2") (pintype "passive"))
    )
    (net (code "71") (name "CAM_DATA_3_0") (class "Default")
      (node (ref "U26") (pin "26") (pinfunction "2A8_26") (pintype "passive"))
    )
    (net (code "72") (name "CAM_DATA_3_1") (class "Default")
      (node (ref "U26") (pin "27") (pinfunction "2A7_27") (pintype "passive"))
    )
    (net (code "73") (name "CAM_DATA_3_2") (class "Default")
      (node (ref "U26") (pin "29") (pinfunction "2A6_29") (pintype "passive"))
    )
    (net (code "74") (name "CAM_DATA_3_3") (class "Default")
      (node (ref "U26") (pin "30") (pinfunction "2A5_30") (pintype "passive"))
    )
    (net (code "75") (name "CAM_DATA_3_4") (class "Default")
      (node (ref "U26") (pin "32") (pinfunction "2A4_32") (pintype "passive"))
    )
    (net (code "76") (name "CAM_DATA_3_5") (class "Default")
      (node (ref "U26") (pin "33") (pinfunction "2A3_33") (pintype "passive"))
    )
    (net (code "77") (name "CAM_DATA_3_6") (class "Default")
      (node (ref "U26") (pin "35") (pinfunction "2A2_35") (pintype "passive"))
    )
    (net (code "78") (name "CAM_DATA_3_7") (class "Default")
      (node (ref "U26") (pin "36") (pinfunction "2A1_36") (pintype "passive"))
    )
    (net (code "79") (name "CAM_DATA_3_8") (class "Default")
      (node (ref "U26") (pin "37") (pinfunction "1A8_37") (pintype "passive"))
    )
    (net (code "80") (name "CAM_DATA_3_9") (class "Default")
      (node (ref "U26") (pin "38") (pinfunction "1A7_38") (pintype "passive"))
    )
    (net (code "81") (name "CAM_DATA_3_10") (class "Default")
      (node (ref "U26") (pin "40") (pinfunction "1A6_40") (pintype "passive"))
    )
    (net (code "82") (name "CAM_DATA_3_11") (class "Default")
      (node (ref "U26") (pin "41") (pinfunction "1A5_41") (pintype "passive"))
    )
    (net (code "83") (name "CAM_DATA_3_12") (class "Default")
      (node (ref "U26") (pin "43") (pinfunction "1A4_43") (pintype "passive"))
    )
    (net (code "84") (name "CAM_DATA_3_13") (class "Default")
      (node (ref "U26") (pin "44") (pinfunction "1A3_44") (pintype "passive"))
    )
    (net (code "85") (name "CAM_DATA_3_14") (class "Default")
      (node (ref "U26") (pin "46") (pinfunction "1A2_46") (pintype "passive"))
    )
    (net (code "86") (name "CAM_DATA_3_15") (class "Default")
      (node (ref "U26") (pin "47") (pinfunction "1A1_47") (pintype "passive"))
    )
    (net (code "87") (name "CAM_DATA_3_16") (class "Default")
      (node (ref "U27") (pin "32") (pinfunction "2A4_32") (pintype "passive"))
    )
    (net (code "88") (name "CAM_DATA_3_17") (class "Default")
      (node (ref "U27") (pin "33") (pinfunction "2A3_33") (pintype "passive"))
    )
    (net (code "89") (name "CAM_DATA_3_18") (class "Default")
      (node (ref "U27") (pin "35") (pinfunction "2A2_35") (pintype "passive"))
    )
    (net (code "90") (name "CAM_DATA_3_19") (class "Default")
      (node (ref "U27") (pin "36") (pinfunction "2A1_36") (pintype "passive"))
    )
    (net (code "91") (name "CAM_DATA_3_20") (class "Default")
      (node (ref "U27") (pin "37") (pinfunction "1A8_37") (pintype "passive"))
    )
    (net (code "92") (name "CAM_DATA_3_21") (class "Default")
      (node (ref "U27") (pin "38") (pinfunction "1A7_38") (pintype "passive"))
    )
    (net (code "93") (name "CAM_DATA_3_22") (class "Default")
      (node (ref "U27") (pin "40") (pinfunction "1A6_40") (pintype "passive"))
    )
    (net (code "94") (name "CAM_DATA_3_23") (class "Default")
      (node (ref "U27") (pin "46") (pinfunction "1A2_46") (pintype "passive"))
    )
    (net (code "95") (name "CAM_DATA_4_0") (class "Default")
      (node (ref "U28") (pin "27") (pinfunction "RXOUT0_27") (pintype "passive"))
    )
    (net (code "96") (name "CAM_DATA_4_1") (class "Default")
      (node (ref "U28") (pin "29") (pinfunction "RXOUT1_29") (pintype "passive"))
    )
    (net (code "97") (name "CAM_DATA_4_2") (class "Default")
      (node (ref "U28") (pin "30") (pinfunction "RXOUT2_30") (pintype "passive"))
    )
    (net (code "98") (name "CAM_DATA_4_3") (class "Default")
      (node (ref "U28") (pin "32") (pinfunction "RXOUT3_32") (pintype "passive"))
    )
    (net (code "99") (name "CAM_DATA_4_4") (class "Default")
      (node (ref "U28") (pin "33") (pinfunction "RXOUT4_33") (pintype "passive"))
    )
    (net (code "100") (name "CAM_DATA_4_5") (class "Default")
      (node (ref "U28") (pin "34") (pinfunction "RXOUT5_34") (pintype "passive"))
    )
    (net (code "101") (name "CAM_DATA_4_6") (class "Default")
      (node (ref "U28") (pin "35") (pinfunction "RXOUT6_35") (pintype "passive"))
    )
    (net (code "102") (name "CAM_DATA_4_7") (class "Default")
      (node (ref "U28") (pin "37") (pinfunction "RXOUT7_37") (pintype "passive"))
    )
    (net (code "103") (name "CAM_DATA_4_8") (class "Default")
      (node (ref "U28") (pin "38") (pinfunction "RXOUT8_38") (pintype "passive"))
    )
    (net (code "104") (name "CAM_DATA_4_9") (class "Default")
      (node (ref "U28") (pin "39") (pinfunction "RXOUT9_39") (pintype "passive"))
    )
    (net (code "105") (name "CAM_DATA_4_10") (class "Default")
      (node (ref "U28") (pin "41") (pinfunction "RXOUT10_41") (pintype "passive"))
    )
    (net (code "106") (name "CAM_DATA_4_11") (class "Default")
      (node (ref "U28") (pin "42") (pinfunction "RXOUT11_42") (pintype "passive"))
    )
    (net (code "107") (name "CAM_DATA_4_12") (class "Default")
      (node (ref "U28") (pin "43") (pinfunction "RXOUT12_43") (pintype "passive"))
    )
    (net (code "108") (name "CAM_DATA_4_13") (class "Default")
      (node (ref "U28") (pin "45") (pinfunction "RXOUT13_45") (pintype "passive"))
    )
    (net (code "109") (name "CAM_DATA_4_14") (class "Default")
      (node (ref "U28") (pin "46") (pinfunction "RXOUT14_46") (pintype "passive"))
    )
    (net (code "110") (name "CAM_DATA_4_15") (class "Default")
      (node (ref "U28") (pin "47") (pinfunction "RXOUT15_47") (pintype "passive"))
    )
    (net (code "111") (name "CAM_DATA_4_16") (class "Default")
      (node (ref "U28") (pin "49") (pinfunction "RXOUT16_49") (pintype "passive"))
    )
    (net (code "112") (name "CAM_DATA_4_17") (class "Default")
      (node (ref "U28") (pin "50") (pinfunction "RXOUT17_50") (pintype "passive"))
    )
    (net (code "113") (name "CAM_DATA_4_18") (class "Default")
      (node (ref "U28") (pin "51") (pinfunction "RXOUT18_51") (pintype "passive"))
    )
    (net (code "114") (name "CAM_DATA_4_19") (class "Default")
      (node (ref "U28") (pin "53") (pinfunction "RXOUT19_53") (pintype "passive"))
    )
    (net (code "115") (name "CAM_DATA_4_20") (class "Default")
      (node (ref "U28") (pin "54") (pinfunction "RXOUT20_54") (pintype "passive"))
    )
    (net (code "116") (name "CAM_DATA_4_21") (class "Default")
      (node (ref "U28") (pin "55") (pinfunction "RXOUT21_55") (pintype "passive"))
    )
    (net (code "117") (name "CAM_DATA_4_22") (class "Default")
      (node (ref "U28") (pin "1") (pinfunction "RXOUT22_1") (pintype "passive"))
    )
    (net (code "118") (name "CAM_DATA_4_23") (class "Default")
      (node (ref "U28") (pin "7") (pinfunction "RXOUT27_7") (pintype "passive"))
    )
    (net (code "119") (name "CARD_CC_3_1") (class "Default")
      (node (ref "U27") (pin "30") (pinfunction "2A5_30") (pintype "passive"))
    )
    (net (code "120") (name "CARD_CC_3_2") (class "Default")
      (node (ref "U27") (pin "29") (pinfunction "2A6_29") (pintype "passive"))
    )
    (net (code "121") (name "CARD_CC_3_3") (class "Default")
      (node (ref "U27") (pin "27") (pinfunction "2A7_27") (pintype "passive"))
    )
    (net (code "122") (name "CARD_CC_3_4") (class "Default")
      (node (ref "U27") (pin "26") (pinfunction "2A8_26") (pintype "passive"))
    )
    (net (code "123") (name "CARD_CC_4_1") (class "Default")
      (node (ref "TP13") (pin "0") (pintype "passive"))
      (node (ref "U29") (pin "7") (pinfunction "DIN4_7") (pintype "passive"))
    )
    (net (code "124") (name "CARD_CC_4_2") (class "Default")
      (node (ref "TP14") (pin "0") (pintype "passive"))
      (node (ref "U29") (pin "6") (pinfunction "DIN3_6") (pintype "passive"))
    )
    (net (code "125") (name "CARD_CC_4_3") (class "Default")
      (node (ref "TP15") (pin "0") (pintype "passive"))
      (node (ref "U29") (pin "3") (pinfunction "DIN2_3") (pintype "passive"))
    )
    (net (code "126") (name "CARD_CC_4_4") (class "Default")
      (node (ref "TP16") (pin "0") (pintype "passive"))
      (node (ref "U29") (pin "2") (pinfunction "DIN1_2") (pintype "passive"))
    )
    (net (code "127") (name "DVAL_3") (class "Default")
      (node (ref "U27") (pin "44") (pinfunction "1A3_44") (pintype "passive"))
    )
    (net (code "128") (name "DVAL_4") (class "Default")
      (node (ref "U28") (pin "6") (pinfunction "RXOUT26_6") (pintype "passive"))
    )
    (net (code "129") (name "FVAL_3") (class "Default")
      (node (ref "U27") (pin "43") (pinfunction "1A4_43") (pintype "passive"))
    )
    (net (code "130") (name "FVAL_4") (class "Default")
      (node (ref "U28") (pin "5") (pinfunction "RXOUT25_5") (pintype "passive"))
    )
    (net (code "131") (name "GND") (class "Default")
      (node (ref "C128") (pin "1") (pinfunction "1_1") (pintype "passive"))
      (node (ref "C129") (pin "1") (pinfunction "1_1") (pintype "passive"))
      (node (ref "C130") (pin "1") (pinfunction "1_1") (pintype "passive"))
      (node (ref "C131") (pin "1") (pinfunction "1_1") (pintype "passive"))
      (node (ref "C132") (pin "1") (pinfunction "1_1") (pintype "passive"))
      (node (ref "C133") (pin "1") (pinfunction "1_1") (pintype "passive"))
      (node (ref "C134") (pin "1") (pinfunction "1_1") (pintype "passive"))
      (node (ref "C135") (pin "1") (pinfunction "1_1") (pintype "passive"))
      (node (ref "C136") (pin "1") (pinfunction "1_1") (pintype "passive"))
      (node (ref "C137") (pin "1") (pinfunction "1_1") (pintype "passive"))
      (node (ref "C138") (pin "1") (pinfunction "1_1") (pintype "passive"))
      (node (ref "C139") (pin "1") (pinfunction "1_1") (pintype "passive"))
      (node (ref "C140") (pin "1") (pinfunction "1_1") (pintype "passive"))
      (node (ref "C141") (pin "1") (pinfunction "1_1") (pintype "passive"))
      (node (ref "C142") (pin "1") (pinfunction "1_1") (pintype "passive"))
      (node (ref "C143") (pin "1") (pinfunction "1_1") (pintype "passive"))
      (node (ref "C144") (pin "1") (pinfunction "1_1") (pintype "passive"))
      (node (ref "C145") (pin "1") (pinfunction "1_1") (pintype "passive"))
      (node (ref "C146") (pin "1") (pinfunction "1_1") (pintype "passive"))
      (node (ref "C147") (pin "1") (pinfunction "1_1") (pintype "passive"))
      (node (ref "C148") (pin "1") (pinfunction "1_1") (pintype "passive"))
      (node (ref "C149") (pin "1") (pinfunction "1_1") (pintype "passive"))
      (node (ref "C150") (pin "1") (pinfunction "1_1") (pintype "passive"))
      (node (ref "C151") (pin "1") (pinfunction "1_1") (pintype "passive"))
      (node (ref "C152") (pin "1") (pinfunction "1_1") (pintype "passive"))
      (node (ref "C153") (pin "1") (pinfunction "1_1") (pintype "passive"))
      (node (ref "C154") (pin "1") (pinfunction "1_1") (pintype "passive"))
      (node (ref "C155") (pin "1") (pinfunction "1_1") (pintype "passive"))
      (node (ref "C156") (pin "1") (pinfunction "1_1") (pintype "passive"))
      (node (ref "C157") (pin "1") (pinfunction "1_1") (pintype "passive"))
      (node (ref "C158") (pin "1") (pinfunction "1_1") (pintype "passive"))
      (node (ref "C159") (pin "1") (pinfunction "1_1") (pintype "passive"))
      (node (ref "C160") (pin "1") (pinfunction "1_1") (pintype "passive"))
      (node (ref "C161") (pin "1") (pinfunction "1_1") (pintype "passive"))
      (node (ref "C162") (pin "1") (pinfunction "1_1") (pintype "passive"))
      (node (ref "C163") (pin "1") (pinfunction "1_1") (pintype "passive"))
      (node (ref "C164") (pin "1") (pinfunction "1_1") (pintype "passive"))
      (node (ref "C165") (pin "1") (pinfunction "1_1") (pintype "passive"))
      (node (ref "C166") (pin "1") (pinfunction "1_1") (pintype "passive"))
      (node (ref "C167") (pin "1") (pinfunction "1_1") (pintype "passive"))
      (node (ref "C168") (pin "1") (pinfunction "1_1") (pintype "passive"))
      (node (ref "C169") (pin "1") (pinfunction "1_1") (pintype "passive"))
      (node (ref "C170") (pin "1") (pinfunction "1_1") (pintype "passive"))
      (node (ref "C171") (pin "1") (pinfunction "1_1") (pintype "passive"))
      (node (ref "J19") (pin "1") (pintype "passive"))
      (node (ref "J19") (pin "13") (pintype "passive"))
      (node (ref "J19") (pin "14") (pintype "passive"))
      (node (ref "J19") (pin "26") (pintype "passive"))
      (node (ref "J19") (pin "27") (pinfunction "27_27") (pintype "passive"))
      (node (ref "J19") (pin "28") (pinfunction "28_28") (pintype "passive"))
      (node (ref "J20") (pin "1") (pintype "passive"))
      (node (ref "J20") (pin "13") (pintype "passive"))
      (node (ref "J20") (pin "14") (pintype "passive"))
      (node (ref "J20") (pin "26") (pintype "passive"))
      (node (ref "J20") (pin "27") (pinfunction "27_27") (pintype "passive"))
      (node (ref "J20") (pin "28") (pinfunction "28_28") (pintype "passive"))
      (node (ref "R102") (pin "2") (pinfunction "2_2") (pintype "passive"))
      (node (ref "R110") (pin "2") (pinfunction "2_2") (pintype "passive"))
      (node (ref "U24") (pin "14") (pinfunction "LVDS_GND_14") (pintype "passive"))
      (node (ref "U24") (pin "21") (pinfunction "LVDS_GND_21") (pintype "passive"))
      (node (ref "U24") (pin "22") (pinfunction "PLL_GND_22") (pintype "passive"))
      (node (ref "U24") (pin "24") (pinfunction "PLL_GND_24") (pintype "passive"))
      (node (ref "U24") (pin "28") (pinfunction "GND_28") (pintype "passive"))
      (node (ref "U24") (pin "36") (pinfunction "GND_36") (pintype "passive"))
      (node (ref "U24") (pin "4") (pinfunction "GND_4") (pintype "passive"))
      (node (ref "U24") (pin "44") (pinfunction "GND_44") (pintype "passive"))
      (node (ref "U24") (pin "52") (pinfunction "GND_52") (pintype "passive"))
      (node (ref "U24") (pin "8") (pinfunction "LVDS_GND_8") (pintype "passive"))
      (node (ref "U25") (pin "5") (pinfunction "GND_5") (pintype "passive"))
      (node (ref "U25") (pin "8") (pinfunction "EN*_8") (pintype "passive"))
      (node (ref "U26") (pin "1") (pinfunction "1DIR_1") (pintype "passive"))
      (node (ref "U26") (pin "10") (pinfunction "GND_10") (pintype "passive"))
      (node (ref "U26") (pin "15") (pinfunction "GND_15") (pintype "passive"))
      (node (ref "U26") (pin "21") (pinfunction "GND_21") (pintype "passive"))
      (node (ref "U26") (pin "24") (pinfunction "2DIR_24") (pintype "passive"))
      (node (ref "U26") (pin "25") (pinfunction "2~{OE}_25") (pintype "passive"))
      (node (ref "U26") (pin "28") (pinfunction "GND_28") (pintype "passive"))
      (node (ref "U26") (pin "34") (pinfunction "GND_34") (pintype "passive"))
      (node (ref "U26") (pin "39") (pinfunction "GND_39") (pintype "passive"))
      (node (ref "U26") (pin "4") (pinfunction "GND_4") (pintype "passive"))
      (node (ref "U26") (pin "45") (pinfunction "GND_45") (pintype "passive"))
      (node (ref "U26") (pin "48") (pinfunction "1~{OE}_48") (pintype "passive"))
      (node (ref "U27") (pin "21") (pinfunction "GND_21") (pintype "passive"))
      (node (ref "U28") (pin "14") (pinfunction "LVDS_GND_14") (pintype "passive"))
      (node (ref "U28") (pin "21") (pinfunction "LVDS_GND_21") (pintype "passive"))
      (node (ref "U28") (pin "22") (pinfunction "PLL_GND_22") (pintype "passive"))
      (node (ref "U28") (pin "24") (pinfunction "PLL_GND_24") (pintype "passive"))
      (node (ref "U28") (pin "28") (pinfunction "GND_28") (pintype "passive"))
      (node (ref "U28") (pin "36") (pinfunction "GND_36") (pintype "passive"))
      (node (ref "U28") (pin "4") (pinfunction "GND_4") (pintype "passive"))
      (node (ref "U28") (pin "44") (pinfunction "GND_44") (pintype "passive"))
      (node (ref "U28") (pin "52") (pinfunction "GND_52") (pintype "passive"))
      (node (ref "U28") (pin "8") (pinfunction "LVDS_GND_8") (pintype "passive"))
      (node (ref "U29") (pin "5") (pinfunction "GND_5") (pintype "passive"))
      (node (ref "U29") (pin "8") (pinfunction "EN*_8") (pintype "passive"))
    )
    (net (code "132") (name "LVAL_3") (class "Default")
      (node (ref "U27") (pin "41") (pinfunction "1A5_41") (pintype "passive"))
    )
    (net (code "133") (name "LVAL_4") (class "Default")
      (node (ref "U28") (pin "3") (pinfunction "RXOUT24_3") (pintype "passive"))
    )
    (net (code "134") (name "Net-(J19-Pad6)") (class "Default")
      (node (ref "J19") (pin "6") (pintype "passive"))
      (node (ref "R101") (pin "1") (pinfunction "1_1") (pintype "passive"))
      (node (ref "R103") (pin "1") (pinfunction "1_1") (pintype "passive"))
    )
    (net (code "135") (name "Net-(J19-Pad19)") (class "Default")
      (node (ref "J19") (pin "19") (pintype "passive"))
      (node (ref "R102") (pin "1") (pinfunction "1_1") (pintype "passive"))
      (node (ref "R103") (pin "2") (pinfunction "2_2") (pintype "passive"))
    )
    (net (code "136") (name "Net-(J20-Pad6)") (class "Default")
      (node (ref "J20") (pin "6") (pintype "passive"))
      (node (ref "R109") (pin "1") (pinfunction "1_1") (pintype "passive"))
      (node (ref "R111") (pin "1") (pinfunction "1_1") (pintype "passive"))
    )
    (net (code "137") (name "Net-(J20-Pad19)") (class "Default")
      (node (ref "J20") (pin "19") (pintype "passive"))
      (node (ref "R110") (pin "1") (pinfunction "1_1") (pintype "passive"))
      (node (ref "R111") (pin "2") (pinfunction "2_2") (pintype "passive"))
    )
    (net (code "138") (name "Net-(U27-1DIR)") (class "Default")
      (node (ref "U27") (pin "1") (pinfunction "1DIR_1") (pintype "passive"))
      (node (ref "U27") (pin "10") (pinfunction "GND_10") (pintype "passive"))
      (node (ref "U27") (pin "15") (pinfunction "GND_15") (pintype "passive"))
      (node (ref "U27") (pin "24") (pinfunction "2DIR_24") (pintype "passive"))
      (node (ref "U27") (pin "25") (pinfunction "2~{OE}_25") (pintype "passive"))
      (node (ref "U27") (pin "28") (pinfunction "GND_28") (pintype "passive"))
      (node (ref "U27") (pin "34") (pinfunction "GND_34") (pintype "passive"))
      (node (ref "U27") (pin "39") (pinfunction "GND_39") (pintype "passive"))
      (node (ref "U27") (pin "4") (pinfunction "GND_4") (pintype "passive"))
      (node (ref "U27") (pin "45") (pinfunction "GND_45") (pintype "passive"))
      (node (ref "U27") (pin "48") (pinfunction "1~{OE}_48") (pintype "passive"))
    )
    (net (code "139") (name "STROBE_3") (class "Default")
      (node (ref "U27") (pin "47") (pinfunction "1A1_47") (pintype "passive"))
    )
    (net (code "140") (name "STROBE_4") (class "Default")
      (node (ref "U28") (pin "26") (pinfunction "RXCLK_OUT_26") (pintype "passive"))
    )
    (net (code "141") (name "unconnected-(J19-Pad7)") (class "Default")
      (node (ref "J19") (pin "7") (pintype "passive+no_connect"))
    )
    (net (code "142") (name "unconnected-(J19-Pad20)") (class "Default")
      (node (ref "J19") (pin "20") (pintype "passive+no_connect"))
    )
    (net (code "143") (name "unconnected-(J20-Pad7)") (class "Default")
      (node (ref "J20") (pin "7") (pintype "passive+no_connect"))
    )
    (net (code "144") (name "unconnected-(J20-Pad20)") (class "Default")
      (node (ref "J20") (pin "20") (pintype "passive+no_connect"))
    )
    (net (code "145") (name "unconnected-(U24-RXOUT23-Pad2)") (class "Default")
      (node (ref "U24") (pin "2") (pinfunction "RXOUT23_2") (pintype "passive+no_connect"))
    )
    (net (code "146") (name "unconnected-(U28-RXOUT23-Pad2)") (class "Default")
      (node (ref "U28") (pin "2") (pinfunction "RXOUT23_2") (pintype "passive+no_connect"))
    )
  )
)
